# incubadora-v2.net
KiCad netlist of a schematic drawn in EAGLE
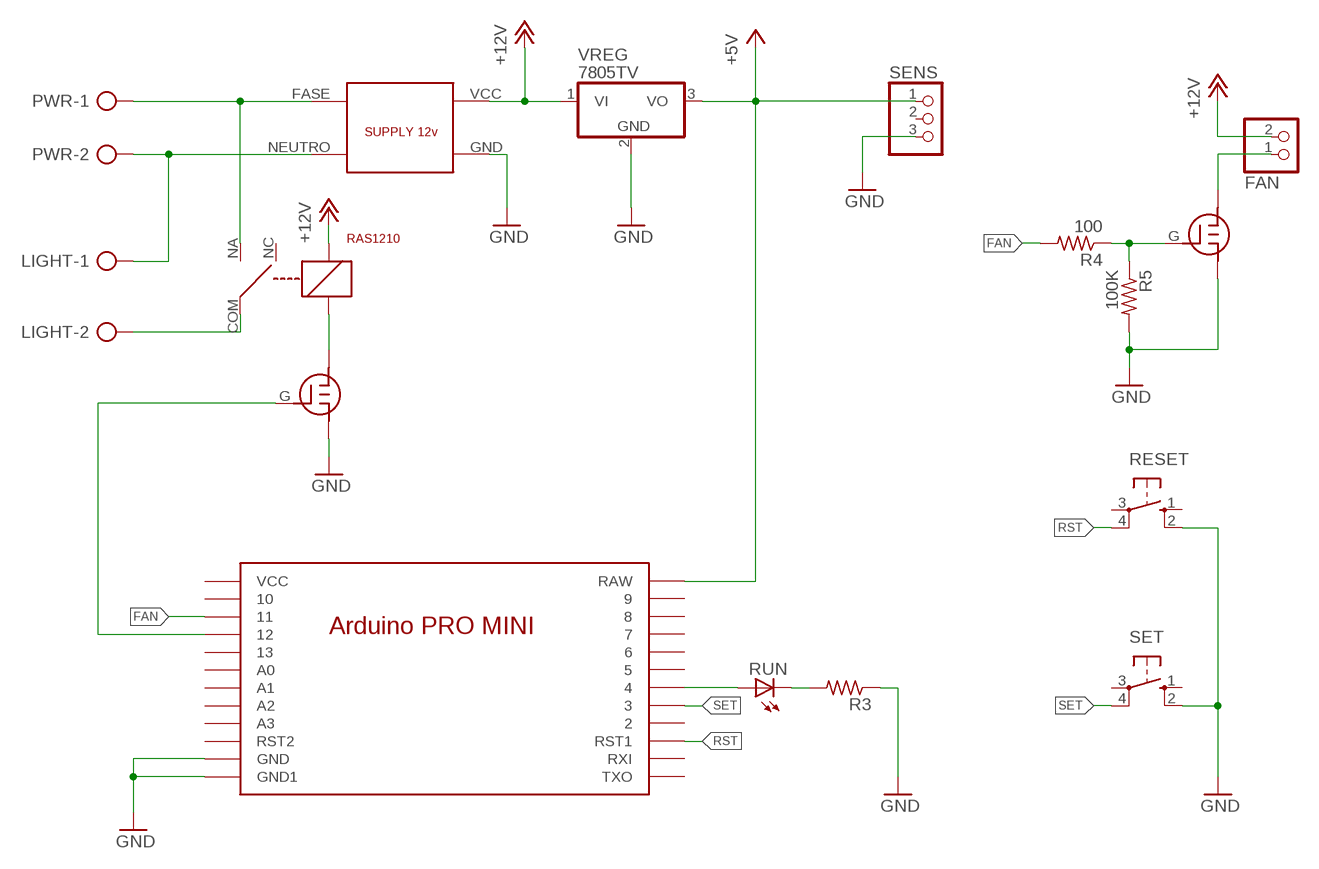
[diagram p0: schematic, sheet 1]

(export (version "E")
  (design (tool "Eeschema 10.0.6"))
  (components
    (comp (ref "FAN")
      (value "PINHD-1X2/90")
      (footprint "eagle-import:1X02_90")
      (libsource (lib "eagle-import") (part "PINHD-1X2/90"))
    )
    (comp (ref "LIGHT")
      (value "AK300/2")
      (footprint "eagle-import:AK300_2")
      (libsource (lib "eagle-import") (part "AK300/2"))
    )
    (comp (ref "PWR")
      (value "AK300/2")
      (footprint "eagle-import:AK300_2")
      (libsource (lib "eagle-import") (part "AK300/2"))
    )
    (comp (ref "R3")
      (value "R-US_0204/7")
      (footprint "eagle-import:0204_7")
      (libsource (lib "eagle-import") (part "R-US_0204/7"))
    )
    (comp (ref "R4")
      (value "100")
      (footprint "eagle-import:0204_7")
      (libsource (lib "eagle-import") (part "R-US_0204/7"))
    )
    (comp (ref "R5")
      (value "100K")
      (footprint "eagle-import:0204_7")
      (libsource (lib "eagle-import") (part "R-US_0204/7"))
    )
    (comp (ref "RAS1210")
      (value "RAS0510")
      (footprint "eagle-import:RAS0510")
      (libsource (lib "eagle-import") (part "RAS0510"))
    )
    (comp (ref "RESET")
      (value "10-XX")
      (footprint "eagle-import:B3F-10XX")
      (fields (field (name "MPN") "B3F-1000"))
      (libsource (lib "eagle-import") (part "10-XX"))
    )
    (comp (ref "RUN")
      (value "LED5MM")
      (footprint "eagle-import:LED5MM")
      (libsource (lib "eagle-import") (part "LED5MM"))
    )
    (comp (ref "SENS")
      (value "PINHD-1X3/90")
      (footprint "eagle-import:1X03_90")
      (libsource (lib "eagle-import") (part "PINHD-1X3/90"))
    )
    (comp (ref "SET")
      (value "10-XX")
      (footprint "eagle-import:B3F-10XX")
      (fields (field (name "MPN") "B3F-1000"))
      (libsource (lib "eagle-import") (part "10-XX"))
    )
    (comp (ref "U$1")
      (value "PROMINI")
      (footprint "eagle-import:PROMINI")
      (libsource (lib "eagle-import") (part "PROMINI"))
    )
    (comp (ref "U$2")
      (value "J111")
      (footprint "eagle-import:J111")
      (libsource (lib "eagle-import") (part "J111"))
    )
    (comp (ref "U$3")
      (value "SUPPLY12V")
      (footprint "eagle-import:SUPPLY12V")
      (libsource (lib "eagle-import") (part "SUPPLY12V"))
    )
    (comp (ref "U$4")
      (value "J111")
      (footprint "eagle-import:J111")
      (libsource (lib "eagle-import") (part "J111"))
    )
    (comp (ref "VREG")
      (value "7805TV")
      (footprint "eagle-import:TO220V")
      (libsource (lib "eagle-import") (part "78TV05"))
    )
  )
  (nets
    (net (code "1") (name "+5V") (class "Default")
      (node (ref "SENS") (pin "1") (pinfunction "1_1") (pintype "passive"))
      (node (ref "U$1") (pin "RAW") (pinfunction "RAW_RAW") (pintype "bidirectional"))
      (node (ref "VREG") (pin "3") (pinfunction "VO_3") (pintype "passive"))
    )
    (net (code "2") (name "+12V") (class "Default")
      (node (ref "FAN") (pin "2") (pinfunction "2_2") (pintype "passive"))
      (node (ref "RAS1210") (pin "B1") (pinfunction "B1_B1") (pintype "bidirectional"))
      (node (ref "U$3") (pin "VCC") (pinfunction "VCC_VCC") (pintype "bidirectional"))
      (node (ref "VREG") (pin "1") (pinfunction "VI_1") (pintype "input"))
    )
    (net (code "3") (name "FAN") (class "Default")
      (node (ref "R4") (pin "2") (pinfunction "2_2") (pintype "passive"))
      (node (ref "U$1") (pin "11") (pinfunction "11_11") (pintype "bidirectional"))
    )
    (net (code "4") (name "GND") (class "Default")
      (node (ref "R3") (pin "1") (pinfunction "1_1") (pintype "passive"))
      (node (ref "R5") (pin "2") (pinfunction "2_2") (pintype "passive"))
      (node (ref "RESET") (pin "2") (pinfunction "S1_2") (pintype "passive"))
      (node (ref "SENS") (pin "3") (pinfunction "3_3") (pintype "passive"))
      (node (ref "SET") (pin "2") (pinfunction "S1_2") (pintype "passive"))
      (node (ref "U$1") (pin "GND1") (pinfunction "GND_GND1") (pintype "bidirectional"))
      (node (ref "U$1") (pin "GND2") (pinfunction "GND1_GND2") (pintype "power_in"))
      (node (ref "U$2") (pin "S") (pinfunction "S_S") (pintype "bidirectional"))
      (node (ref "U$3") (pin "GND") (pinfunction "GND_GND") (pintype "bidirectional"))
      (node (ref "U$4") (pin "S") (pinfunction "S_S") (pintype "bidirectional"))
      (node (ref "VREG") (pin "2") (pinfunction "GND_2") (pintype "passive"))
    )
    (net (code "5") (name "Net-(FAN-Pad1)") (class "Default")
      (node (ref "FAN") (pin "1") (pinfunction "1_1") (pintype "passive"))
      (node (ref "U$2") (pin "D") (pinfunction "D_D") (pintype "bidirectional"))
    )
    (net (code "6") (name "Net-(LIGHTA-KL)") (class "Default")
      (node (ref "LIGHT") (pin "1") (pinfunction "KL_1") (pintype "passive"))
      (node (ref "PWR") (pin "2") (pinfunction "KL_2") (pintype "passive"))
      (node (ref "U$3") (pin "NEUTRO") (pinfunction "NEUTRO_NEUTRO") (pintype "bidirectional"))
    )
    (net (code "7") (name "Net-(LIGHTB-KL)") (class "Default")
      (node (ref "LIGHT") (pin "2") (pinfunction "KL_2") (pintype "passive"))
      (node (ref "RAS1210") (pin "COM") (pinfunction "COM_COM") (pintype "bidirectional"))
    )
    (net (code "8") (name "Net-(PWRA-KL)") (class "Default")
      (node (ref "PWR") (pin "1") (pinfunction "KL_1") (pintype "passive"))
      (node (ref "RAS1210") (pin "NA") (pinfunction "NA_NA") (pintype "bidirectional"))
      (node (ref "U$3") (pin "FASE") (pinfunction "FASE_FASE") (pintype "bidirectional"))
    )
    (net (code "9") (name "Net-(R4-Pad1)") (class "Default")
      (node (ref "R4") (pin "1") (pinfunction "1_1") (pintype "passive"))
      (node (ref "R5") (pin "1") (pinfunction "1_1") (pintype "passive"))
      (node (ref "U$2") (pin "G") (pinfunction "G_G") (pintype "bidirectional"))
    )
    (net (code "10") (name "Net-(RAS1210-PadB2)") (class "Default")
      (node (ref "RAS1210") (pin "B2") (pinfunction "B2_B2") (pintype "bidirectional"))
      (node (ref "U$4") (pin "D") (pinfunction "D_D") (pintype "bidirectional"))
    )
    (net (code "11") (name "Net-(RUN-C)") (class "Default")
      (node (ref "R3") (pin "2") (pinfunction "2_2") (pintype "passive"))
      (node (ref "RUN") (pin "K") (pinfunction "C_K") (pintype "passive"))
    )
    (net (code "12") (name "Net-(RUN-PadA)") (class "Default")
      (node (ref "RUN") (pin "A") (pinfunction "A_A") (pintype "passive"))
      (node (ref "U$1") (pin "4") (pinfunction "4_4") (pintype "bidirectional"))
    )
    (net (code "13") (name "Net-(U$1-Pad12)") (class "Default")
      (node (ref "U$1") (pin "12") (pinfunction "12_12") (pintype "bidirectional"))
      (node (ref "U$4") (pin "G") (pinfunction "G_G") (pintype "bidirectional"))
    )
    (net (code "14") (name "RST") (class "Default")
      (node (ref "RESET") (pin "4") (pinfunction "P1_4") (pintype "passive"))
      (node (ref "U$1") (pin "RST1") (pinfunction "RST1_RST1") (pintype "bidirectional"))
    )
    (net (code "15") (name "SET") (class "Default")
      (node (ref "SET") (pin "4") (pinfunction "P1_4") (pintype "passive"))
      (node (ref "U$1") (pin "3") (pinfunction "3_3") (pintype "bidirectional"))
    )
    (net (code "16") (name "unconnected-(RAS1210-PadNC)") (class "Default")
      (node (ref "RAS1210") (pin "NC") (pinfunction "NC_NC") (pintype "bidirectional"))
    )
    (net (code "17") (name "unconnected-(RESET-P-Pad3)") (class "Default")
      (node (ref "RESET") (pin "3") (pinfunction "P_3") (pintype "passive"))
    )
    (net (code "18") (name "unconnected-(RESET-S-Pad1)") (class "Default")
      (node (ref "RESET") (pin "1") (pinfunction "S_1") (pintype "passive"))
    )
    (net (code "19") (name "unconnected-(SENS-Pad2)") (class "Default")
      (node (ref "SENS") (pin "2") (pinfunction "2_2") (pintype "passive"))
    )
    (net (code "20") (name "unconnected-(SET-P-Pad3)") (class "Default")
      (node (ref "SET") (pin "3") (pinfunction "P_3") (pintype "passive"))
    )
    (net (code "21") (name "unconnected-(SET-S-Pad1)") (class "Default")
      (node (ref "SET") (pin "1") (pinfunction "S_1") (pintype "passive"))
    )
    (net (code "22") (name "unconnected-(U$1-Pad2)") (class "Default")
      (node (ref "U$1") (pin "2") (pinfunction "2_2") (pintype "bidirectional"))
    )
    (net (code "23") (name "unconnected-(U$1-Pad5)") (class "Default")
      (node (ref "U$1") (pin "5") (pinfunction "5_5") (pintype "bidirectional"))
    )
    (net (code "24") (name "unconnected-(U$1-Pad6)") (class "Default")
      (node (ref "U$1") (pin "6") (pinfunction "6_6") (pintype "bidirectional"))
    )
    (net (code "25") (name "unconnected-(U$1-Pad7)") (class "Default")
      (node (ref "U$1") (pin "7") (pinfunction "7_7") (pintype "bidirectional"))
    )
    (net (code "26") (name "unconnected-(U$1-Pad8)") (class "Default")
      (node (ref "U$1") (pin "8") (pinfunction "8_8") (pintype "bidirectional"))
    )
    (net (code "27") (name "unconnected-(U$1-Pad9)") (class "Default")
      (node (ref "U$1") (pin "9") (pinfunction "9_9") (pintype "bidirectional"))
    )
    (net (code "28") (name "unconnected-(U$1-Pad10)") (class "Default")
      (node (ref "U$1") (pin "10") (pinfunction "10_10") (pintype "bidirectional"))
    )
    (net (code "29") (name "unconnected-(U$1-Pad13)") (class "Default")
      (node (ref "U$1") (pin "13") (pinfunction "13_13") (pintype "bidirectional"))
    )
    (net (code "30") (name "unconnected-(U$1-PadA0)") (class "Default")
      (node (ref "U$1") (pin "A0") (pinfunction "A0_A0") (pintype "bidirectional"))
    )
    (net (code "31") (name "unconnected-(U$1-PadA1)") (class "Default")
      (node (ref "U$1") (pin "A1") (pinfunction "A1_A1") (pintype "bidirectional"))
    )
    (net (code "32") (name "unconnected-(U$1-PadA2)") (class "Default")
      (node (ref "U$1") (pin "A2") (pinfunction "A2_A2") (pintype "bidirectional"))
    )
    (net (code "33") (name "unconnected-(U$1-PadA3)") (class "Default")
      (node (ref "U$1") (pin "A3") (pinfunction "A3_A3") (pintype "bidirectional"))
    )
    (net (code "34") (name "unconnected-(U$1-PadRST2)") (class "Default")
      (node (ref "U$1") (pin "RST2") (pinfunction "RST2_RST2") (pintype "bidirectional"))
    )
    (net (code "35") (name "unconnected-(U$1-PadRXI)") (class "Default")
      (node (ref "U$1") (pin "RXI") (pinfunction "RXI_RXI") (pintype "bidirectional"))
    )
    (net (code "36") (name "unconnected-(U$1-PadTXO)") (class "Default")
      (node (ref "U$1") (pin "TXO") (pinfunction "TXO_TXO") (pintype "bidirectional"))
    )
    (net (code "37") (name "unconnected-(U$1-PadVCC)") (class "Default")
      (node (ref "U$1") (pin "VCC") (pinfunction "VCC_VCC") (pintype "bidirectional"))
    )
  )
)
